# Baxandall_ne5532.net
KiCad netlist of a schematic drawn in EAGLE
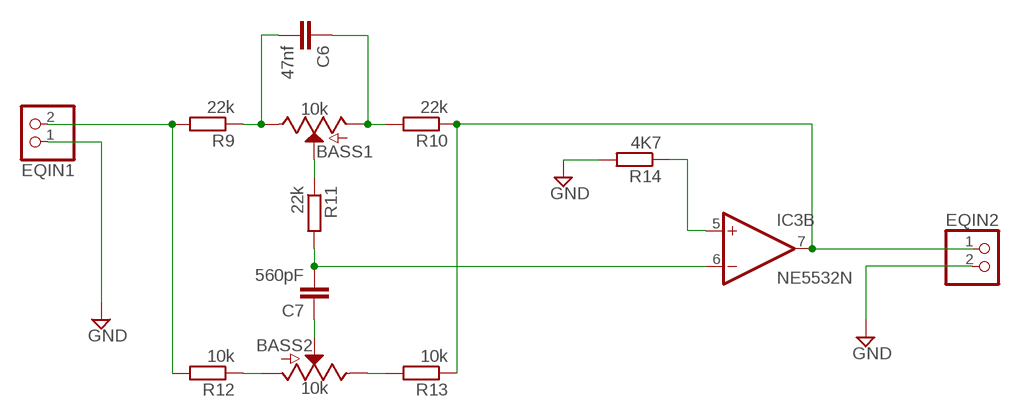
[diagram p0: schematic, sheet 1]

(export (version "E")
  (design (tool "Eeschema 10.0.6"))
  (components
    (comp (ref "BASS1")
      (value "10k")
      (footprint "eagle-import:POT-PTH-ALPS")
      (libsource (lib "eagle-import") (part "POTENTIOMETER-PTH-9MM-1/20W-20%"))
    )
    (comp (ref "BASS2")
      (value "10k")
      (footprint "eagle-import:POT-PTH-ALPS")
      (libsource (lib "eagle-import") (part "POTENTIOMETER-PTH-9MM-1/20W-20%"))
    )
    (comp (ref "C6")
      (value "47nf")
      (footprint "eagle-import:C2.5-2")
      (libsource (lib "eagle-import") (part "C2.5/2"))
    )
    (comp (ref "C7")
      (value "560pF")
      (footprint "eagle-import:C2.5-2")
      (libsource (lib "eagle-import") (part "C2.5/2"))
    )
    (comp (ref "EQIN1")
      (value "PINHD-1X2")
      (footprint "eagle-import:1X02")
      (libsource (lib "eagle-import") (part "PINHD-1X2"))
    )
    (comp (ref "EQIN2")
      (value "PINHD-1X2")
      (footprint "eagle-import:1X02")
      (libsource (lib "eagle-import") (part "PINHD-1X2"))
    )
    (comp (ref "IC3")
      (value "NE5532N")
      (footprint "eagle-import:DIL08")
      (libsource (lib "eagle-import") (part "NE5532N"))
    )
    (comp (ref "R9")
      (value "22k")
      (footprint "eagle-import:0204_7")
      (libsource (lib "eagle-import") (part "R-EU_0204/7"))
    )
    (comp (ref "R10")
      (value "22k")
      (footprint "eagle-import:0204_7")
      (libsource (lib "eagle-import") (part "R-EU_0204/7"))
    )
    (comp (ref "R11")
      (value "22k")
      (footprint "eagle-import:0204_7")
      (libsource (lib "eagle-import") (part "R-EU_0204/7"))
    )
    (comp (ref "R12")
      (value "10k")
      (footprint "eagle-import:0204_7")
      (libsource (lib "eagle-import") (part "R-EU_0204/7"))
    )
    (comp (ref "R13")
      (value "10k")
      (footprint "eagle-import:0204_7")
      (libsource (lib "eagle-import") (part "R-EU_0204/7"))
    )
    (comp (ref "R14")
      (value "4K7")
      (footprint "eagle-import:0204_7")
      (libsource (lib "eagle-import") (part "R-EU_0204/7"))
    )
  )
  (nets
    (net (code "1") (name "GND") (class "Default")
      (node (ref "EQIN1") (pin "1") (pinfunction "1_1") (pintype "passive"))
      (node (ref "EQIN2") (pin "2") (pinfunction "2_2") (pintype "passive"))
      (node (ref "R14") (pin "2") (pinfunction "2_2") (pintype "passive"))
    )
    (net (code "2") (name "Net-(BASS1-A)") (class "Default")
      (node (ref "BASS1") (pin "P$3") (pinfunction "A_P$3") (pintype "passive"))
      (node (ref "C6") (pin "1") (pinfunction "1_1") (pintype "passive"))
      (node (ref "R10") (pin "2") (pinfunction "2_2") (pintype "passive"))
    )
    (net (code "3") (name "Net-(BASS1-E)") (class "Default")
      (node (ref "BASS1") (pin "P$1") (pinfunction "E_P$1") (pintype "passive"))
      (node (ref "C6") (pin "2") (pinfunction "2_2") (pintype "passive"))
      (node (ref "R9") (pin "1") (pinfunction "1_1") (pintype "passive"))
    )
    (net (code "4") (name "Net-(BASS1-S)") (class "Default")
      (node (ref "BASS1") (pin "P$2") (pinfunction "S_P$2") (pintype "passive"))
      (node (ref "R11") (pin "1") (pinfunction "1_1") (pintype "passive"))
    )
    (net (code "5") (name "Net-(BASS2-A)") (class "Default")
      (node (ref "BASS2") (pin "P$3") (pinfunction "A_P$3") (pintype "passive"))
      (node (ref "R12") (pin "1") (pinfunction "1_1") (pintype "passive"))
    )
    (net (code "6") (name "Net-(BASS2-E)") (class "Default")
      (node (ref "BASS2") (pin "P$1") (pinfunction "E_P$1") (pintype "passive"))
      (node (ref "R13") (pin "2") (pinfunction "2_2") (pintype "passive"))
    )
    (net (code "7") (name "Net-(BASS2-S)") (class "Default")
      (node (ref "BASS2") (pin "P$2") (pinfunction "S_P$2") (pintype "passive"))
      (node (ref "C7") (pin "1") (pinfunction "1_1") (pintype "passive"))
    )
    (net (code "8") (name "Net-(EQIN1-Pad2)") (class "Default")
      (node (ref "EQIN1") (pin "2") (pinfunction "2_2") (pintype "passive"))
      (node (ref "R12") (pin "2") (pinfunction "2_2") (pintype "passive"))
      (node (ref "R9") (pin "2") (pinfunction "2_2") (pintype "passive"))
    )
    (net (code "9") (name "Net-(IC3B-+IN)") (class "Default")
      (node (ref "IC3") (pin "5") (pinfunction "+IN_5") (pintype "input"))
      (node (ref "R14") (pin "1") (pinfunction "1_1") (pintype "passive"))
    )
    (net (code "10") (name "Net-(IC3B--IN)") (class "Default")
      (node (ref "C7") (pin "2") (pinfunction "2_2") (pintype "passive"))
      (node (ref "IC3") (pin "6") (pinfunction "-IN_6") (pintype "input"))
      (node (ref "R11") (pin "2") (pinfunction "2_2") (pintype "passive"))
    )
    (net (code "11") (name "Net-(IC3B-OUT)") (class "Default")
      (node (ref "EQIN2") (pin "1") (pinfunction "1_1") (pintype "passive"))
      (node (ref "IC3") (pin "7") (pinfunction "OUT_7") (pintype "output"))
      (node (ref "R10") (pin "1") (pinfunction "1_1") (pintype "passive"))
      (node (ref "R13") (pin "1") (pinfunction "1_1") (pintype "passive"))
    )
  )
)
